# TestBoard.net
KiCad netlist of a schematic drawn in EAGLE
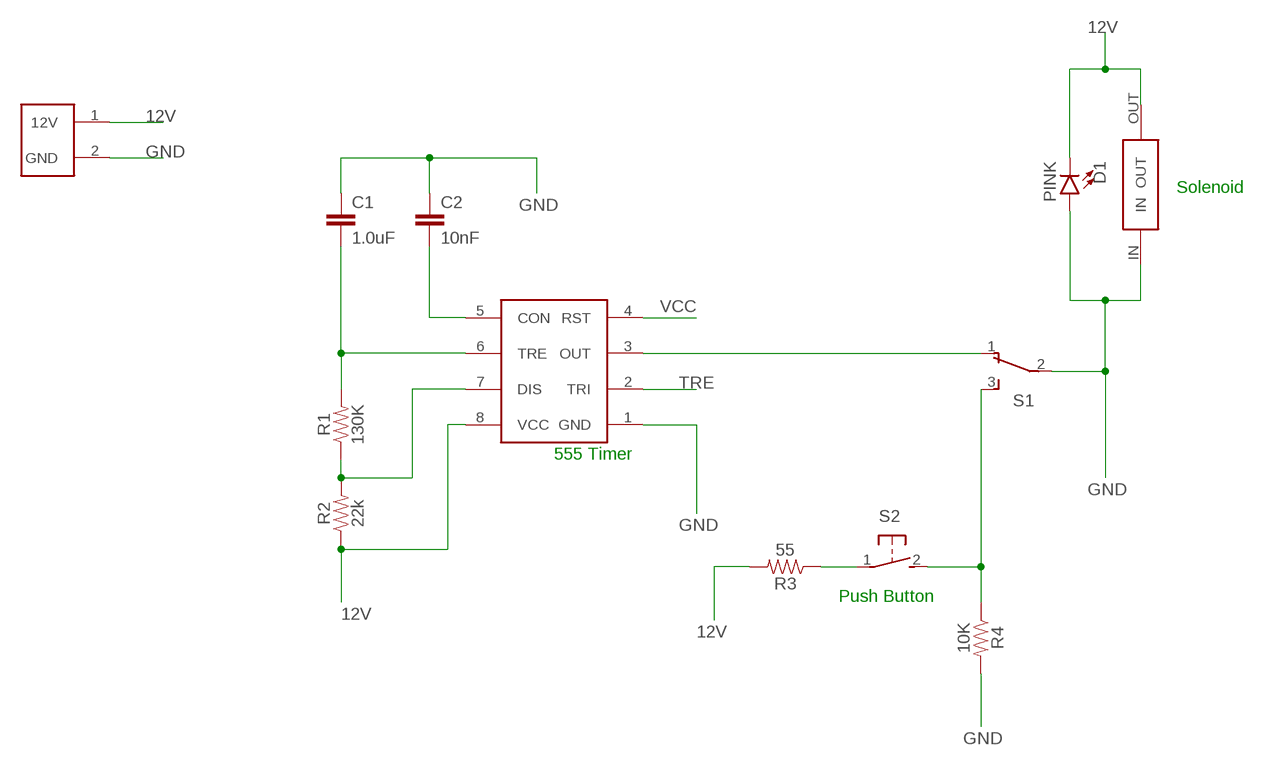
[diagram p0: schematic, sheet 1]

(export (version "E")
  (design (tool "Eeschema 10.0.6"))
  (components
    (comp (ref "C1")
      (value "1.0uF")
      (footprint "eagle-import:0402")
      (libsource (lib "eagle-import") (part "1.0UF-0402-16V-10%"))
    )
    (comp (ref "C2")
      (value "10nF")
      (footprint "eagle-import:0603")
      (libsource (lib "eagle-import") (part "10NF-0603-50V-10%"))
    )
    (comp (ref "D1")
      (value "PINK")
      (footprint "eagle-import:LED-1206")
      (libsource (lib "eagle-import") (part "LED-PINK1206"))
    )
    (comp (ref "R1")
      (value "130K")
      (footprint "eagle-import:0805")
      (libsource (lib "eagle-import") (part "0.22OHM-0805-1/4W-1%"))
    )
    (comp (ref "R2")
      (value "22k")
      (footprint "eagle-import:0805")
      (libsource (lib "eagle-import") (part "0.22OHM-0805-1/4W-1%"))
    )
    (comp (ref "R3")
      (value "55")
      (footprint "eagle-import:0805")
      (libsource (lib "eagle-import") (part "0.22OHM-0805-1/4W-1%"))
    )
    (comp (ref "R4")
      (value "10K")
      (footprint "eagle-import:0805")
      (libsource (lib "eagle-import") (part "0.22OHM-0805-1/4W-1%"))
    )
    (comp (ref "S1")
      (value "TL36YO")
      (footprint "eagle-import:TL3XYO")
      (libsource (lib "eagle-import") (part "TL36YO"))
    )
    (comp (ref "S2")
      (value "31-XX")
      (footprint "eagle-import:B3F-31XX")
      (fields (field (name "MPN") "B3F-3100"))
      (libsource (lib "eagle-import") (part "31-XX"))
    )
    (comp (ref "U$1")
      (value "555TIMER")
      (footprint "eagle-import:555TIME")
      (libsource (lib "eagle-import") (part "555TIMER"))
    )
    (comp (ref "U$2")
      (value "BARRELJACK")
      (footprint "eagle-import:BARRELJACK")
      (libsource (lib "eagle-import") (part "BARRELJACK"))
    )
    (comp (ref "U$3")
      (value "SOLENOID")
      (footprint "eagle-import:SOL")
      (libsource (lib "eagle-import") (part "SOLENOID"))
    )
  )
  (nets
    (net (code "1") (name "/12V") (class "Default")
      (node (ref "D1") (pin "C") (pinfunction "C_C") (pintype "passive"))
      (node (ref "R2") (pin "1") (pinfunction "1_1") (pintype "passive"))
      (node (ref "R3") (pin "2") (pinfunction "2_2") (pintype "passive"))
      (node (ref "U$1") (pin "8") (pinfunction "VCC_8") (pintype "bidirectional"))
      (node (ref "U$2") (pin "1") (pinfunction "12V_1") (pintype "bidirectional"))
      (node (ref "U$3") (pin "OUT") (pinfunction "OUT_OUT") (pintype "bidirectional"))
    )
    (net (code "2") (name "/GND") (class "Default")
      (node (ref "C1") (pin "1") (pinfunction "1_1") (pintype "passive"))
      (node (ref "C2") (pin "1") (pinfunction "1_1") (pintype "passive"))
      (node (ref "D1") (pin "A") (pinfunction "A_A") (pintype "passive"))
      (node (ref "R4") (pin "2") (pinfunction "2_2") (pintype "passive"))
      (node (ref "S1") (pin "2") (pinfunction "P_2") (pintype "passive"))
      (node (ref "U$1") (pin "1") (pinfunction "GND_1") (pintype "bidirectional"))
      (node (ref "U$2") (pin "2") (pinfunction "GND_2") (pintype "bidirectional"))
      (node (ref "U$3") (pin "IN") (pinfunction "IN_IN") (pintype "bidirectional"))
    )
    (net (code "3") (name "/TRE") (class "Default")
      (node (ref "U$1") (pin "2") (pinfunction "TRI_2") (pintype "bidirectional"))
    )
    (net (code "4") (name "/VCC") (class "Default")
      (node (ref "U$1") (pin "4") (pinfunction "RST_4") (pintype "bidirectional"))
    )
    (net (code "5") (name "Net-(S1-O)") (class "Default")
      (node (ref "S1") (pin "1") (pinfunction "O_1") (pintype "passive"))
      (node (ref "U$1") (pin "3") (pinfunction "OUT_3") (pintype "bidirectional"))
    )
    (net (code "6") (name "Net-(S1-S)") (class "Default")
      (node (ref "R4") (pin "1") (pinfunction "1_1") (pintype "passive"))
      (node (ref "S1") (pin "3") (pinfunction "S_3") (pintype "passive"))
      (node (ref "S2") (pin "2") (pinfunction "S_2") (pintype "passive"))
    )
    (net (code "7") (name "Net-(S2-P)") (class "Default")
      (node (ref "R3") (pin "1") (pinfunction "1_1") (pintype "passive"))
      (node (ref "S2") (pin "1") (pinfunction "P_1") (pintype "passive"))
    )
    (net (code "8") (name "Net-(U$1-CON)") (class "Default")
      (node (ref "C2") (pin "2") (pinfunction "2_2") (pintype "passive"))
      (node (ref "U$1") (pin "5") (pinfunction "CON_5") (pintype "bidirectional"))
    )
    (net (code "9") (name "Net-(U$1-DIS)") (class "Default")
      (node (ref "R1") (pin "1") (pinfunction "1_1") (pintype "passive"))
      (node (ref "R2") (pin "2") (pinfunction "2_2") (pintype "passive"))
      (node (ref "U$1") (pin "7") (pinfunction "DIS_7") (pintype "bidirectional"))
    )
    (net (code "10") (name "Net-(U$1-TRE)") (class "Default")
      (node (ref "C1") (pin "2") (pinfunction "2_2") (pintype "passive"))
      (node (ref "R1") (pin "2") (pinfunction "2_2") (pintype "passive"))
      (node (ref "U$1") (pin "6") (pinfunction "TRE_6") (pintype "bidirectional"))
    )
  )
)
